# hdmi_transmitter.net
KiCad netlist of a schematic drawn in EAGLE
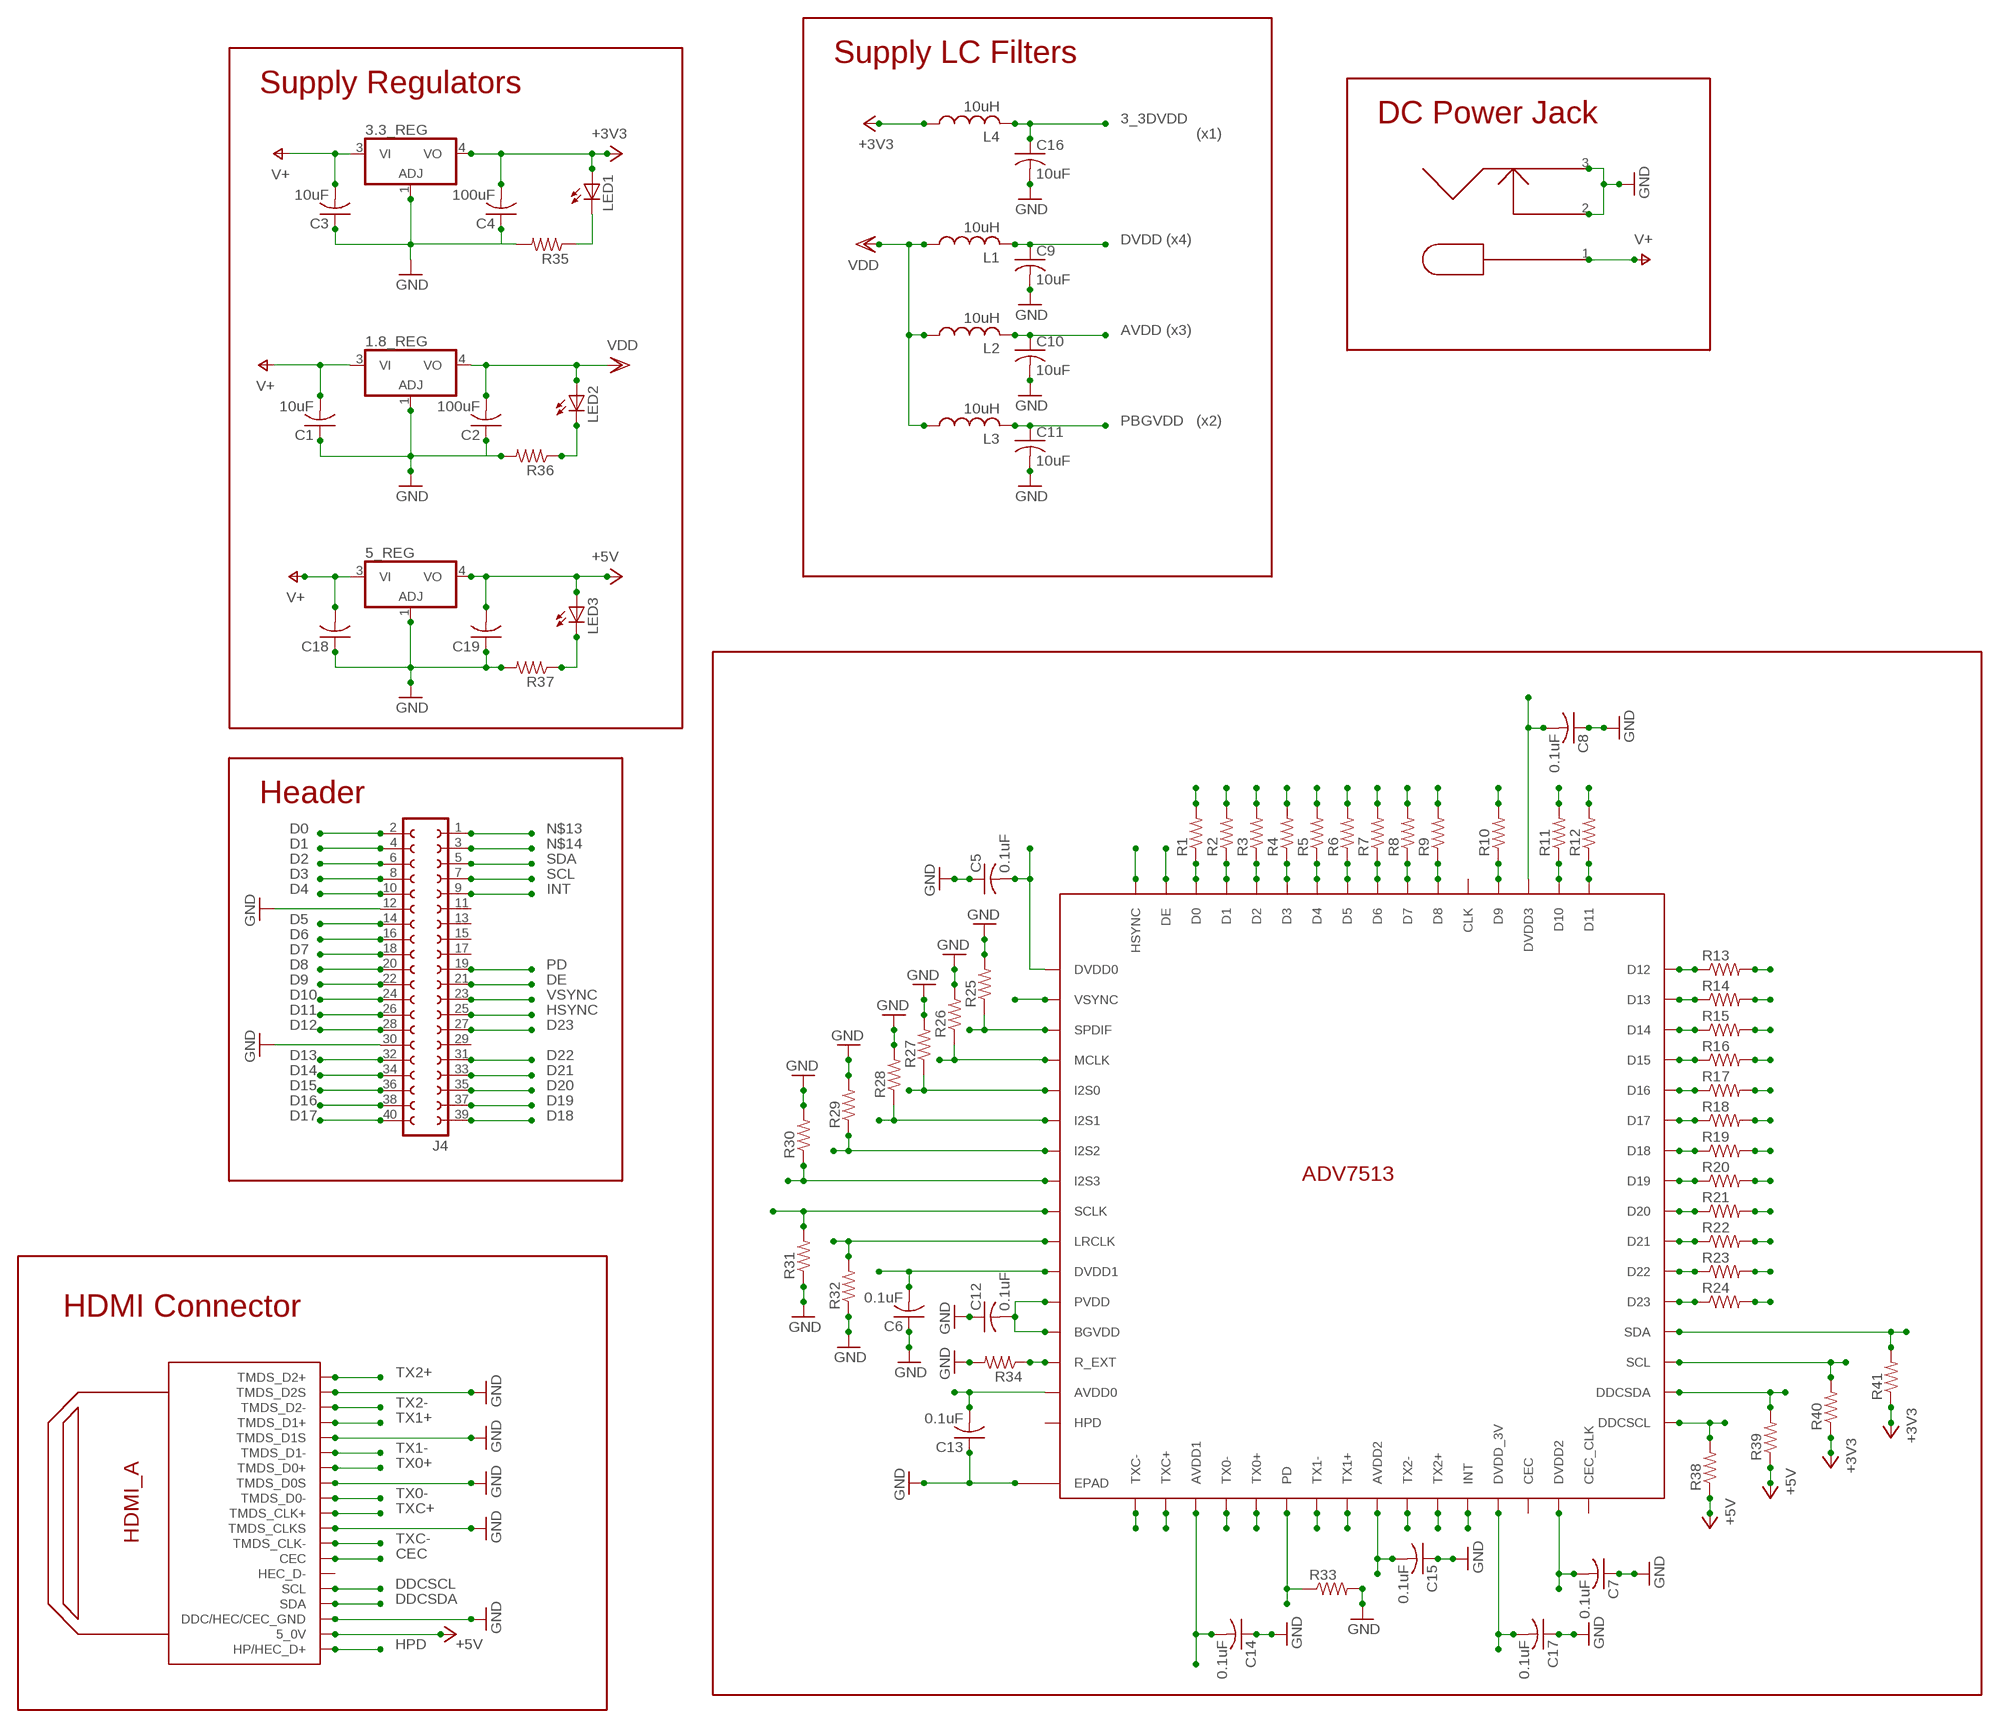
[diagram p0: schematic, sheet 1]

(export (version "E")
  (design (tool "Eeschema 10.0.6"))
  (components
    (comp (ref "1.8_REG")
      (value "317EMP")
      (footprint "eagle-import:SOT223")
      (libsource (lib "eagle-import") (part "317EMP"))
    )
    (comp (ref "3.3_REG")
      (value "317EMP")
      (footprint "eagle-import:SOT223")
      (libsource (lib "eagle-import") (part "317EMP"))
    )
    (comp (ref "5_REG")
      (value "317EMP")
      (footprint "eagle-import:SOT223")
      (libsource (lib "eagle-import") (part "317EMP"))
    )
    (comp (ref "C1")
      (value "10uF")
      (footprint "eagle-import:C0603")
      (libsource (lib "eagle-import") (part "C-USC0603"))
    )
    (comp (ref "C2")
      (value "100uF")
      (footprint "eagle-import:C0603")
      (libsource (lib "eagle-import") (part "C-USC0603"))
    )
    (comp (ref "C3")
      (value "10uF")
      (footprint "eagle-import:C0603")
      (libsource (lib "eagle-import") (part "C-USC0603"))
    )
    (comp (ref "C4")
      (value "100uF")
      (footprint "eagle-import:C0603")
      (libsource (lib "eagle-import") (part "C-USC0603"))
    )
    (comp (ref "C5")
      (value "0.1uF")
      (footprint "eagle-import:C0603")
      (libsource (lib "eagle-import") (part "C-USC0603"))
    )
    (comp (ref "C6")
      (value "0.1uF")
      (footprint "eagle-import:C0603")
      (libsource (lib "eagle-import") (part "C-USC0603"))
    )
    (comp (ref "C7")
      (value "0.1uF")
      (footprint "eagle-import:C0603")
      (libsource (lib "eagle-import") (part "C-USC0603"))
    )
    (comp (ref "C8")
      (value "0.1uF")
      (footprint "eagle-import:C0603")
      (libsource (lib "eagle-import") (part "C-USC0603"))
    )
    (comp (ref "C9")
      (value "10uF")
      (footprint "eagle-import:C0603")
      (libsource (lib "eagle-import") (part "C-USC0603"))
    )
    (comp (ref "C10")
      (value "10uF")
      (footprint "eagle-import:C0603")
      (libsource (lib "eagle-import") (part "C-USC0603"))
    )
    (comp (ref "C11")
      (value "10uF")
      (footprint "eagle-import:C0603")
      (libsource (lib "eagle-import") (part "C-USC0603"))
    )
    (comp (ref "C12")
      (value "0.1uF")
      (footprint "eagle-import:C0603")
      (libsource (lib "eagle-import") (part "C-USC0603"))
    )
    (comp (ref "C13")
      (value "0.1uF")
      (footprint "eagle-import:C0603")
      (libsource (lib "eagle-import") (part "C-USC0603"))
    )
    (comp (ref "C14")
      (value "0.1uF")
      (footprint "eagle-import:C0603")
      (libsource (lib "eagle-import") (part "C-USC0603"))
    )
    (comp (ref "C15")
      (value "0.1uF")
      (footprint "eagle-import:C0603")
      (libsource (lib "eagle-import") (part "C-USC0603"))
    )
    (comp (ref "C16")
      (value "10uF")
      (footprint "eagle-import:C0603")
      (libsource (lib "eagle-import") (part "C-USC0603"))
    )
    (comp (ref "C17")
      (value "0.1uF")
      (footprint "eagle-import:C0603")
      (libsource (lib "eagle-import") (part "C-USC0603"))
    )
    (comp (ref "C18")
      (value "C-USC0603")
      (footprint "eagle-import:C0603")
      (libsource (lib "eagle-import") (part "C-USC0603"))
    )
    (comp (ref "C19")
      (value "C-USC0603")
      (footprint "eagle-import:C0603")
      (libsource (lib "eagle-import") (part "C-USC0603"))
    )
    (comp (ref "J4")
      (value "FE20-2")
      (footprint "eagle-import:FE20-2")
      (libsource (lib "eagle-import") (part "FE20-2"))
    )
    (comp (ref "L1")
      (value "10uH")
      (footprint "eagle-import:L2012C")
      (libsource (lib "eagle-import") (part "L-USL2012C"))
    )
    (comp (ref "L2")
      (value "10uH")
      (footprint "eagle-import:L2012C")
      (libsource (lib "eagle-import") (part "L-USL2012C"))
    )
    (comp (ref "L3")
      (value "10uH")
      (footprint "eagle-import:L2012C")
      (libsource (lib "eagle-import") (part "L-USL2012C"))
    )
    (comp (ref "L4")
      (value "10uH")
      (footprint "eagle-import:L2012C")
      (libsource (lib "eagle-import") (part "L-USL2012C"))
    )
    (comp (ref "LED1")
      (value "LED5MM")
      (footprint "eagle-import:LED5MM")
      (libsource (lib "eagle-import") (part "LED5MM"))
    )
    (comp (ref "LED2")
      (value "LED5MM")
      (footprint "eagle-import:LED5MM")
      (libsource (lib "eagle-import") (part "LED5MM"))
    )
    (comp (ref "LED3")
      (value "LED5MM")
      (footprint "eagle-import:LED5MM")
      (libsource (lib "eagle-import") (part "LED5MM"))
    )
    (comp (ref "R1")
      (value "R-US_R0603")
      (footprint "eagle-import:R0603")
      (libsource (lib "eagle-import") (part "R-US_R0603"))
    )
    (comp (ref "R2")
      (value "R-US_R0603")
      (footprint "eagle-import:R0603")
      (libsource (lib "eagle-import") (part "R-US_R0603"))
    )
    (comp (ref "R3")
      (value "R-US_R0603")
      (footprint "eagle-import:R0603")
      (libsource (lib "eagle-import") (part "R-US_R0603"))
    )
    (comp (ref "R4")
      (value "R-US_R0603")
      (footprint "eagle-import:R0603")
      (libsource (lib "eagle-import") (part "R-US_R0603"))
    )
    (comp (ref "R5")
      (value "R-US_R0603")
      (footprint "eagle-import:R0603")
      (libsource (lib "eagle-import") (part "R-US_R0603"))
    )
    (comp (ref "R6")
      (value "R-US_R0603")
      (footprint "eagle-import:R0603")
      (libsource (lib "eagle-import") (part "R-US_R0603"))
    )
    (comp (ref "R7")
      (value "R-US_R0603")
      (footprint "eagle-import:R0603")
      (libsource (lib "eagle-import") (part "R-US_R0603"))
    )
    (comp (ref "R8")
      (value "R-US_R0603")
      (footprint "eagle-import:R0603")
      (libsource (lib "eagle-import") (part "R-US_R0603"))
    )
    (comp (ref "R9")
      (value "R-US_R0603")
      (footprint "eagle-import:R0603")
      (libsource (lib "eagle-import") (part "R-US_R0603"))
    )
    (comp (ref "R10")
      (value "R-US_R0603")
      (footprint "eagle-import:R0603")
      (libsource (lib "eagle-import") (part "R-US_R0603"))
    )
    (comp (ref "R11")
      (value "R-US_R0603")
      (footprint "eagle-import:R0603")
      (libsource (lib "eagle-import") (part "R-US_R0603"))
    )
    (comp (ref "R12")
      (value "R-US_R0603")
      (footprint "eagle-import:R0603")
      (libsource (lib "eagle-import") (part "R-US_R0603"))
    )
    (comp (ref "R13")
      (value "R-US_R0603")
      (footprint "eagle-import:R0603")
      (libsource (lib "eagle-import") (part "R-US_R0603"))
    )
    (comp (ref "R14")
      (value "R-US_R0603")
      (footprint "eagle-import:R0603")
      (libsource (lib "eagle-import") (part "R-US_R0603"))
    )
    (comp (ref "R15")
      (value "R-US_R0603")
      (footprint "eagle-import:R0603")
      (libsource (lib "eagle-import") (part "R-US_R0603"))
    )
    (comp (ref "R16")
      (value "R-US_R0603")
      (footprint "eagle-import:R0603")
      (libsource (lib "eagle-import") (part "R-US_R0603"))
    )
    (comp (ref "R17")
      (value "R-US_R0603")
      (footprint "eagle-import:R0603")
      (libsource (lib "eagle-import") (part "R-US_R0603"))
    )
    (comp (ref "R18")
      (value "R-US_R0603")
      (footprint "eagle-import:R0603")
      (libsource (lib "eagle-import") (part "R-US_R0603"))
    )
    (comp (ref "R19")
      (value "R-US_R0603")
      (footprint "eagle-import:R0603")
      (libsource (lib "eagle-import") (part "R-US_R0603"))
    )
    (comp (ref "R20")
      (value "R-US_R0603")
      (footprint "eagle-import:R0603")
      (libsource (lib "eagle-import") (part "R-US_R0603"))
    )
    (comp (ref "R21")
      (value "R-US_R0603")
      (footprint "eagle-import:R0603")
      (libsource (lib "eagle-import") (part "R-US_R0603"))
    )
    (comp (ref "R22")
      (value "R-US_R0603")
      (footprint "eagle-import:R0603")
      (libsource (lib "eagle-import") (part "R-US_R0603"))
    )
    (comp (ref "R23")
      (value "R-US_R0603")
      (footprint "eagle-import:R0603")
      (libsource (lib "eagle-import") (part "R-US_R0603"))
    )
    (comp (ref "R24")
      (value "R-US_R0603")
      (footprint "eagle-import:R0603")
      (libsource (lib "eagle-import") (part "R-US_R0603"))
    )
    (comp (ref "R25")
      (value "R-US_R0603")
      (footprint "eagle-import:R0603")
      (libsource (lib "eagle-import") (part "R-US_R0603"))
    )
    (comp (ref "R26")
      (value "R-US_R0603")
      (footprint "eagle-import:R0603")
      (libsource (lib "eagle-import") (part "R-US_R0603"))
    )
    (comp (ref "R27")
      (value "R-US_R0603")
      (footprint "eagle-import:R0603")
      (libsource (lib "eagle-import") (part "R-US_R0603"))
    )
    (comp (ref "R28")
      (value "R-US_R0603")
      (footprint "eagle-import:R0603")
      (libsource (lib "eagle-import") (part "R-US_R0603"))
    )
    (comp (ref "R29")
      (value "R-US_R0603")
      (footprint "eagle-import:R0603")
      (libsource (lib "eagle-import") (part "R-US_R0603"))
    )
    (comp (ref "R30")
      (value "R-US_R0603")
      (footprint "eagle-import:R0603")
      (libsource (lib "eagle-import") (part "R-US_R0603"))
    )
    (comp (ref "R31")
      (value "R-US_R0603")
      (footprint "eagle-import:R0603")
      (libsource (lib "eagle-import") (part "R-US_R0603"))
    )
    (comp (ref "R32")
      (value "R-US_R0603")
      (footprint "eagle-import:R0603")
      (libsource (lib "eagle-import") (part "R-US_R0603"))
    )
    (comp (ref "R33")
      (value "R-US_R0603")
      (footprint "eagle-import:R0603")
      (libsource (lib "eagle-import") (part "R-US_R0603"))
    )
    (comp (ref "R34")
      (value "R-US_R0603")
      (footprint "eagle-import:R0603")
      (libsource (lib "eagle-import") (part "R-US_R0603"))
    )
    (comp (ref "R35")
      (value "R-US_R0603")
      (footprint "eagle-import:R0603")
      (libsource (lib "eagle-import") (part "R-US_R0603"))
    )
    (comp (ref "R36")
      (value "R-US_R0603")
      (footprint "eagle-import:R0603")
      (libsource (lib "eagle-import") (part "R-US_R0603"))
    )
    (comp (ref "R37")
      (value "R-US_R0603")
      (footprint "eagle-import:R0603")
      (libsource (lib "eagle-import") (part "R-US_R0603"))
    )
    (comp (ref "R38")
      (value "R-US_R0603")
      (footprint "eagle-import:R0603")
      (libsource (lib "eagle-import") (part "R-US_R0603"))
    )
    (comp (ref "R39")
      (value "R-US_R0603")
      (footprint "eagle-import:R0603")
      (libsource (lib "eagle-import") (part "R-US_R0603"))
    )
    (comp (ref "R40")
      (value "R-US_R0603")
      (footprint "eagle-import:R0603")
      (libsource (lib "eagle-import") (part "R-US_R0603"))
    )
    (comp (ref "R41")
      (value "R-US_R0603")
      (footprint "eagle-import:R0603")
      (libsource (lib "eagle-import") (part "R-US_R0603"))
    )
    (comp (ref "U$1")
      (value "ADV7513")
      (footprint "eagle-import:LQFP-ST-64-2")
      (libsource (lib "eagle-import") (part "ADV7513"))
    )
    (comp (ref "U$2")
      (value "DC_BARREL_CONN")
      (footprint "eagle-import:DC_BARREL_CONN")
      (libsource (lib "eagle-import") (part "DC_BARREL_CONN"))
    )
    (comp (ref "U$3")
      (value "111RLF")
      (footprint "eagle-import:111RLF")
      (libsource (lib "eagle-import") (part "111RLF"))
    )
  )
  (nets
    (net (code "1") (name "+3V3") (class "Default")
      (node (ref "3.3_REG") (pin "4") (pinfunction "VO_4") (pintype "passive"))
      (node (ref "C4") (pin "2") (pinfunction "2_2") (pintype "passive"))
      (node (ref "L4") (pin "1") (pinfunction "1_1") (pintype "passive"))
      (node (ref "LED1") (pin "A") (pinfunction "A_A") (pintype "passive"))
      (node (ref "R40") (pin "1") (pinfunction "1_1") (pintype "passive"))
      (node (ref "R41") (pin "1") (pinfunction "1_1") (pintype "passive"))
    )
    (net (code "2") (name "+5V") (class "Default")
      (node (ref "5_REG") (pin "4") (pinfunction "VO_4") (pintype "passive"))
      (node (ref "C19") (pin "2") (pinfunction "2_2") (pintype "passive"))
      (node (ref "LED3") (pin "A") (pinfunction "A_A") (pintype "passive"))
      (node (ref "R38") (pin "1") (pinfunction "1_1") (pintype "passive"))
      (node (ref "R39") (pin "1") (pinfunction "1_1") (pintype "passive"))
      (node (ref "U$3") (pin "18") (pinfunction "5_0V_18") (pintype "bidirectional"))
    )
    (net (code "3") (name "/3_3DVDD") (class "Default")
      (node (ref "C16") (pin "1") (pinfunction "1_1") (pintype "passive"))
      (node (ref "C17") (pin "2") (pinfunction "2_2") (pintype "passive"))
      (node (ref "L4") (pin "2") (pinfunction "2_2") (pintype "passive"))
      (node (ref "U$1") (pin "29") (pinfunction "DVDD_3V_29") (pintype "bidirectional"))
    )
    (net (code "4") (name "/AVDD") (class "Default")
      (node (ref "C10") (pin "1") (pinfunction "1_1") (pintype "passive"))
      (node (ref "C13") (pin "2") (pinfunction "2_2") (pintype "passive"))
      (node (ref "C14") (pin "2") (pinfunction "2_2") (pintype "passive"))
      (node (ref "C15") (pin "2") (pinfunction "2_2") (pintype "passive"))
      (node (ref "L2") (pin "2") (pinfunction "2_2") (pintype "passive"))
      (node (ref "U$1") (pin "15") (pinfunction "AVDD0_15") (pintype "bidirectional"))
      (node (ref "U$1") (pin "19") (pinfunction "AVDD1_19") (pintype "bidirectional"))
      (node (ref "U$1") (pin "25") (pinfunction "AVDD2_25") (pintype "bidirectional"))
    )
    (net (code "5") (name "/CEC") (class "Default")
      (node (ref "U$3") (pin "13") (pinfunction "CEC_13") (pintype "bidirectional"))
    )
    (net (code "6") (name "/D0") (class "Default")
      (node (ref "J4") (pin "2") (pinfunction "2_2") (pintype "passive"))
      (node (ref "R1") (pin "2") (pinfunction "2_2") (pintype "passive"))
    )
    (net (code "7") (name "/D1") (class "Default")
      (node (ref "J4") (pin "4") (pinfunction "4_4") (pintype "passive"))
      (node (ref "R2") (pin "2") (pinfunction "2_2") (pintype "passive"))
    )
    (net (code "8") (name "/D2") (class "Default")
      (node (ref "J4") (pin "6") (pinfunction "6_6") (pintype "passive"))
      (node (ref "R3") (pin "2") (pinfunction "2_2") (pintype "passive"))
    )
    (net (code "9") (name "/D3") (class "Default")
      (node (ref "J4") (pin "8") (pinfunction "8_8") (pintype "passive"))
      (node (ref "R4") (pin "2") (pinfunction "2_2") (pintype "passive"))
    )
    (net (code "10") (name "/D4") (class "Default")
      (node (ref "J4") (pin "10") (pinfunction "10_10") (pintype "passive"))
      (node (ref "R5") (pin "2") (pinfunction "2_2") (pintype "passive"))
    )
    (net (code "11") (name "/D5") (class "Default")
      (node (ref "J4") (pin "14") (pinfunction "14_14") (pintype "passive"))
      (node (ref "R6") (pin "2") (pinfunction "2_2") (pintype "passive"))
    )
    (net (code "12") (name "/D6") (class "Default")
      (node (ref "J4") (pin "16") (pinfunction "16_16") (pintype "passive"))
      (node (ref "R7") (pin "2") (pinfunction "2_2") (pintype "passive"))
    )
    (net (code "13") (name "/D7") (class "Default")
      (node (ref "J4") (pin "18") (pinfunction "18_18") (pintype "passive"))
      (node (ref "R8") (pin "2") (pinfunction "2_2") (pintype "passive"))
    )
    (net (code "14") (name "/D8") (class "Default")
      (node (ref "J4") (pin "20") (pinfunction "20_20") (pintype "passive"))
      (node (ref "R9") (pin "2") (pinfunction "2_2") (pintype "passive"))
    )
    (net (code "15") (name "/D9") (class "Default")
      (node (ref "J4") (pin "22") (pinfunction "22_22") (pintype "passive"))
      (node (ref "R10") (pin "2") (pinfunction "2_2") (pintype "passive"))
    )
    (net (code "16") (name "/D10") (class "Default")
      (node (ref "J4") (pin "24") (pinfunction "24_24") (pintype "passive"))
      (node (ref "R11") (pin "2") (pinfunction "2_2") (pintype "passive"))
    )
    (net (code "17") (name "/D11") (class "Default")
      (node (ref "J4") (pin "26") (pinfunction "26_26") (pintype "passive"))
      (node (ref "R12") (pin "2") (pinfunction "2_2") (pintype "passive"))
    )
    (net (code "18") (name "/D12") (class "Default")
      (node (ref "J4") (pin "28") (pinfunction "28_28") (pintype "passive"))
      (node (ref "R13") (pin "2") (pinfunction "2_2") (pintype "passive"))
    )
    (net (code "19") (name "/D13") (class "Default")
      (node (ref "J4") (pin "32") (pinfunction "32_32") (pintype "passive"))
      (node (ref "R14") (pin "2") (pinfunction "2_2") (pintype "passive"))
    )
    (net (code "20") (name "/D14") (class "Default")
      (node (ref "J4") (pin "34") (pinfunction "34_34") (pintype "passive"))
      (node (ref "R15") (pin "2") (pinfunction "2_2") (pintype "passive"))
    )
    (net (code "21") (name "/D15") (class "Default")
      (node (ref "J4") (pin "36") (pinfunction "36_36") (pintype "passive"))
      (node (ref "R16") (pin "2") (pinfunction "2_2") (pintype "passive"))
    )
    (net (code "22") (name "/D16") (class "Default")
      (node (ref "J4") (pin "38") (pinfunction "38_38") (pintype "passive"))
      (node (ref "R17") (pin "2") (pinfunction "2_2") (pintype "passive"))
    )
    (net (code "23") (name "/D17") (class "Default")
      (node (ref "J4") (pin "40") (pinfunction "40_40") (pintype "passive"))
      (node (ref "R18") (pin "2") (pinfunction "2_2") (pintype "passive"))
    )
    (net (code "24") (name "/D18") (class "Default")
      (node (ref "J4") (pin "39") (pinfunction "39_39") (pintype "passive"))
      (node (ref "R19") (pin "2") (pinfunction "2_2") (pintype "passive"))
    )
    (net (code "25") (name "/D19") (class "Default")
      (node (ref "J4") (pin "37") (pinfunction "37_37") (pintype "passive"))
      (node (ref "R20") (pin "2") (pinfunction "2_2") (pintype "passive"))
    )
    (net (code "26") (name "/D20") (class "Default")
      (node (ref "J4") (pin "35") (pinfunction "35_35") (pintype "passive"))
      (node (ref "R21") (pin "2") (pinfunction "2_2") (pintype "passive"))
    )
    (net (code "27") (name "/D21") (class "Default")
      (node (ref "J4") (pin "33") (pinfunction "33_33") (pintype "passive"))
      (node (ref "R22") (pin "2") (pinfunction "2_2") (pintype "passive"))
    )
    (net (code "28") (name "/D22") (class "Default")
      (node (ref "J4") (pin "31") (pinfunction "31_31") (pintype "passive"))
      (node (ref "R23") (pin "2") (pinfunction "2_2") (pintype "passive"))
    )
    (net (code "29") (name "/D23") (class "Default")
      (node (ref "J4") (pin "27") (pinfunction "27_27") (pintype "passive"))
      (node (ref "R24") (pin "2") (pinfunction "2_2") (pintype "passive"))
    )
    (net (code "30") (name "/DDCSCL") (class "Default")
      (node (ref "R38") (pin "2") (pinfunction "2_2") (pintype "passive"))
      (node (ref "U$1") (pin "33") (pinfunction "DDCSCL_33") (pintype "bidirectional"))
      (node (ref "U$3") (pin "15") (pinfunction "SCL_15") (pintype "bidirectional"))
    )
    (net (code "31") (name "/DDCSDA") (class "Default")
      (node (ref "R39") (pin "2") (pinfunction "2_2") (pintype "passive"))
      (node (ref "U$1") (pin "34") (pinfunction "DDCSDA_34") (pintype "bidirectional"))
      (node (ref "U$3") (pin "16") (pinfunction "SDA_16") (pintype "bidirectional"))
    )
    (net (code "32") (name "/DE") (class "Default")
      (node (ref "J4") (pin "21") (pinfunction "21_21") (pintype "passive"))
      (node (ref "U$1") (pin "63") (pinfunction "DE_63") (pintype "bidirectional"))
    )
    (net (code "33") (name "/DVDD") (class "Default")
      (node (ref "C5") (pin "2") (pinfunction "2_2") (pintype "passive"))
      (node (ref "C6") (pin "2") (pinfunction "2_2") (pintype "passive"))
      (node (ref "C7") (pin "2") (pinfunction "2_2") (pintype "passive"))
      (node (ref "C8") (pin "2") (pinfunction "2_2") (pintype "passive"))
      (node (ref "C9") (pin "1") (pinfunction "1_1") (pintype "passive"))
      (node (ref "L1") (pin "2") (pinfunction "2_2") (pintype "passive"))
      (node (ref "U$1") (pin "1") (pinfunction "DVDD0_1") (pintype "bidirectional"))
      (node (ref "U$1") (pin "11") (pinfunction "DVDD1_11") (pintype "bidirectional"))
      (node (ref "U$1") (pin "31") (pinfunction "DVDD2_31") (pintype "bidirectional"))
      (node (ref "U$1") (pin "51") (pinfunction "DVDD3_51") (pintype "bidirectional"))
    )
    (net (code "34") (name "/HPD") (class "Default")
      (node (ref "U$3") (pin "19") (pinfunction "HP/HEC_D+_19") (pintype "bidirectional"))
    )
    (net (code "35") (name "/HSYNC") (class "Default")
      (node (ref "J4") (pin "25") (pinfunction "25_25") (pintype "passive"))
      (node (ref "U$1") (pin "64") (pinfunction "HSYNC_64") (pintype "bidirectional"))
    )
    (net (code "36") (name "/INT") (class "Default")
      (node (ref "J4") (pin "9") (pinfunction "9_9") (pintype "passive"))
      (node (ref "U$1") (pin "28") (pinfunction "INT_28") (pintype "bidirectional"))
    )
    (net (code "37") (name "/N$13") (class "Default")
      (node (ref "J4") (pin "1") (pinfunction "1_1") (pintype "passive"))
    )
    (net (code "38") (name "/N$14") (class "Default")
      (node (ref "J4") (pin "3") (pinfunction "3_3") (pintype "passive"))
    )
    (net (code "39") (name "/PBGVDD") (class "Default")
      (node (ref "C11") (pin "1") (pinfunction "1_1") (pintype "passive"))
      (node (ref "C12") (pin "2") (pinfunction "2_2") (pintype "passive"))
      (node (ref "L3") (pin "2") (pinfunction "2_2") (pintype "passive"))
      (node (ref "U$1") (pin "12") (pinfunction "PVDD_12") (pintype "bidirectional"))
      (node (ref "U$1") (pin "13") (pinfunction "BGVDD_13") (pintype "bidirectional"))
    )
    (net (code "40") (name "/PD") (class "Default")
      (node (ref "J4") (pin "19") (pinfunction "19_19") (pintype "passive"))
      (node (ref "R33") (pin "1") (pinfunction "1_1") (pintype "passive"))
      (node (ref "U$1") (pin "22") (pinfunction "PD_22") (pintype "bidirectional"))
    )
    (net (code "41") (name "/SCL") (class "Default")
      (node (ref "J4") (pin "7") (pinfunction "7_7") (pintype "passive"))
      (node (ref "R40") (pin "2") (pinfunction "2_2") (pintype "passive"))
      (node (ref "U$1") (pin "35") (pinfunction "SCL_35") (pintype "bidirectional"))
    )
    (net (code "42") (name "/SDA") (class "Default")
      (node (ref "J4") (pin "5") (pinfunction "5_5") (pintype "passive"))
      (node (ref "R41") (pin "2") (pinfunction "2_2") (pintype "passive"))
      (node (ref "U$1") (pin "36") (pinfunction "SDA_36") (pintype "bidirectional"))
    )
    (net (code "43") (name "/TX0+") (class "Default")
      (node (ref "U$1") (pin "21") (pinfunction "TX0+_21") (pintype "bidirectional"))
      (node (ref "U$3") (pin "7") (pinfunction "TMDS_D0+_7") (pintype "bidirectional"))
    )
    (net (code "44") (name "/TX0-") (class "Default")
      (node (ref "U$1") (pin "20") (pinfunction "TX0-_20") (pintype "bidirectional"))
      (node (ref "U$3") (pin "9") (pinfunction "TMDS_D0-_9") (pintype "bidirectional"))
    )
    (net (code "45") (name "/TX1+") (class "Default")
      (node (ref "U$1") (pin "24") (pinfunction "TX1+_24") (pintype "bidirectional"))
      (node (ref "U$3") (pin "4") (pinfunction "TMDS_D1+_4") (pintype "bidirectional"))
    )
    (net (code "46") (name "/TX1-") (class "Default")
      (node (ref "U$1") (pin "23") (pinfunction "TX1-_23") (pintype "bidirectional"))
      (node (ref "U$3") (pin "6") (pinfunction "TMDS_D1-_6") (pintype "bidirectional"))
    )
    (net (code "47") (name "/TX2+") (class "Default")
      (node (ref "U$1") (pin "27") (pinfunction "TX2+_27") (pintype "bidirectional"))
      (node (ref "U$3") (pin "1") (pinfunction "TMDS_D2+_1") (pintype "bidirectional"))
    )
    (net (code "48") (name "/TX2-") (class "Default")
      (node (ref "U$1") (pin "26") (pinfunction "TX2-_26") (pintype "bidirectional"))
      (node (ref "U$3") (pin "3") (pinfunction "TMDS_D2-_3") (pintype "bidirectional"))
    )
    (net (code "49") (name "/TXC+") (class "Default")
      (node (ref "U$1") (pin "18") (pinfunction "TXC+_18") (pintype "bidirectional"))
      (node (ref "U$3") (pin "10") (pinfunction "TMDS_CLK+_10") (pintype "bidirectional"))
    )
    (net (code "50") (name "/TXC-") (class "Default")
      (node (ref "U$1") (pin "17") (pinfunction "TXC-_17") (pintype "bidirectional"))
      (node (ref "U$3") (pin "12") (pinfunction "TMDS_CLK-_12") (pintype "bidirectional"))
    )
    (net (code "51") (name "/VSYNC") (class "Default")
      (node (ref "J4") (pin "23") (pinfunction "23_23") (pintype "passive"))
      (node (ref "U$1") (pin "2") (pinfunction "VSYNC_2") (pintype "bidirectional"))
    )
    (net (code "52") (name "GND") (class "Default")
      (node (ref "1.8_REG") (pin "1") (pinfunction "ADJ_1") (pintype "input"))
      (node (ref "3.3_REG") (pin "1") (pinfunction "ADJ_1") (pintype "input"))
      (node (ref "5_REG") (pin "1") (pinfunction "ADJ_1") (pintype "input"))
      (node (ref "C1") (pin "1") (pinfunction "1_1") (pintype "passive"))
      (node (ref "C10") (pin "2") (pinfunction "2_2") (pintype "passive"))
      (node (ref "C11") (pin "2") (pinfunction "2_2") (pintype "passive"))
      (node (ref "C12") (pin "1") (pinfunction "1_1") (pintype "passive"))
      (node (ref "C13") (pin "1") (pinfunction "1_1") (pintype "passive"))
      (node (ref "C14") (pin "1") (pinfunction "1_1") (pintype "passive"))
      (node (ref "C15") (pin "1") (pinfunction "1_1") (pintype "passive"))
      (node (ref "C16") (pin "2") (pinfunction "2_2") (pintype "passive"))
      (node (ref "C17") (pin "1") (pinfunction "1_1") (pintype "passive"))
      (node (ref "C18") (pin "1") (pinfunction "1_1") (pintype "passive"))
      (node (ref "C19") (pin "1") (pinfunction "1_1") (pintype "passive"))
      (node (ref "C2") (pin "1") (pinfunction "1_1") (pintype "passive"))
      (node (ref "C3") (pin "1") (pinfunction "1_1") (pintype "passive"))
      (node (ref "C4") (pin "1") (pinfunction "1_1") (pintype "passive"))
      (node (ref "C5") (pin "1") (pinfunction "1_1") (pintype "passive"))
      (node (ref "C6") (pin "1") (pinfunction "1_1") (pintype "passive"))
      (node (ref "C7") (pin "1") (pinfunction "1_1") (pintype "passive"))
      (node (ref "C8") (pin "1") (pinfunction "1_1") (pintype "passive"))
      (node (ref "C9") (pin "2") (pinfunction "2_2") (pintype "passive"))
      (node (ref "J4") (pin "12") (pinfunction "12_12") (pintype "passive"))
      (node (ref "J4") (pin "30") (pinfunction "30_30") (pintype "passive"))
      (node (ref "R25") (pin "2") (pinfunction "2_2") (pintype "passive"))
      (node (ref "R26") (pin "2") (pinfunction "2_2") (pintype "passive"))
      (node (ref "R27") (pin "2") (pinfunction "2_2") (pintype "passive"))
      (node (ref "R28") (pin "2") (pinfunction "2_2") (pintype "passive"))
      (node (ref "R29") (pin "2") (pinfunction "2_2") (pintype "passive"))
      (node (ref "R30") (pin "2") (pinfunction "2_2") (pintype "passive"))
      (node (ref "R31") (pin "1") (pinfunction "1_1") (pintype "passive"))
      (node (ref "R32") (pin "1") (pinfunction "1_1") (pintype "passive"))
      (node (ref "R33") (pin "2") (pinfunction "2_2") (pintype "passive"))
      (node (ref "R34") (pin "2") (pinfunction "2_2") (pintype "passive"))
      (node (ref "R35") (pin "2") (pinfunction "2_2") (pintype "passive"))
      (node (ref "R36") (pin "2") (pinfunction "2_2") (pintype "passive"))
      (node (ref "R37") (pin "2") (pinfunction "2_2") (pintype "passive"))
      (node (ref "U$1") (pin "0") (pinfunction "EPAD_0") (pintype "bidirectional"))
      (node (ref "U$2") (pin "2") (pinfunction "2_2") (pintype "bidirectional"))
      (node (ref "U$2") (pin "3") (pinfunction "3_3") (pintype "bidirectional"))
      (node (ref "U$3") (pin "11") (pinfunction "TMDS_CLKS_11") (pintype "bidirectional"))
      (node (ref "U$3") (pin "17") (pinfunction "DDC/HEC/CEC_GND_17") (pintype "bidirectional"))
      (node (ref "U$3") (pin "2") (pinfunction "TMDS_D2S_2") (pintype "bidirectional"))
      (node (ref "U$3") (pin "5") (pinfunction "TMDS_D1S_5") (pintype "bidirectional"))
      (node (ref "U$3") (pin "8") (pinfunction "TMDS_D0S_8") (pintype "bidirectional"))
    )
    (net (code "53") (name "Net-(LED1-C)") (class "Default")
      (node (ref "LED1") (pin "K") (pinfunction "C_K") (pintype "passive"))
      (node (ref "R35") (pin "1") (pinfunction "1_1") (pintype "passive"))
    )
    (net (code "54") (name "Net-(LED2-C)") (class "Default")
      (node (ref "LED2") (pin "K") (pinfunction "C_K") (pintype "passive"))
      (node (ref "R36") (pin "1") (pinfunction "1_1") (pintype "passive"))
    )
    (net (code "55") (name "Net-(LED3-C)") (class "Default")
      (node (ref "LED3") (pin "K") (pinfunction "C_K") (pintype "passive"))
      (node (ref "R37") (pin "1") (pinfunction "1_1") (pintype "passive"))
    )
    (net (code "56") (name "Net-(U$1-D0)") (class "Default")
      (node (ref "R1") (pin "1") (pinfunction "1_1") (pintype "passive"))
      (node (ref "U$1") (pin "62") (pinfunction "D0_62") (pintype "bidirectional"))
    )
    (net (code "57") (name "Net-(U$1-D1)") (class "Default")
      (node (ref "R2") (pin "1") (pinfunction "1_1") (pintype "passive"))
      (node (ref "U$1") (pin "61") (pinfunction "D1_61") (pintype "bidirectional"))
    )
    (net (code "58") (name "Net-(U$1-D2)") (class "Default")
      (node (ref "R3") (pin "1") (pinfunction "1_1") (pintype "passive"))
      (node (ref "U$1") (pin "60") (pinfunction "D2_60") (pintype "bidirectional"))
    )
    (net (code "59") (name "Net-(U$1-D3)") (class "Default")
      (node (ref "R4") (pin "1") (pinfunction "1_1") (pintype "passive"))
      (node (ref "U$1") (pin "59") (pinfunction "D3_59") (pintype "bidirectional"))
    )
    (net (code "60") (name "Net-(U$1-D4)") (class "Default")
      (node (ref "R5") (pin "1") (pinfunction "1_1") (pintype "passive"))
      (node (ref "U$1") (pin "58") (pinfunction "D4_58") (pintype "bidirectional"))
    )
    (net (code "61") (name "Net-(U$1-D5)") (class "Default")
      (node (ref "R6") (pin "1") (pinfunction "1_1") (pintype "passive"))
      (node (ref "U$1") (pin "57") (pinfunction "D5_57") (pintype "bidirectional"))
    )
    (net (code "62") (name "Net-(U$1-D6)") (class "Default")
      (node (ref "R7") (pin "1") (pinfunction "1_1") (pintype "passive"))
      (node (ref "U$1") (pin "56") (pinfunction "D6_56") (pintype "bidirectional"))
    )
    (net (code "63") (name "Net-(U$1-D7)") (class "Default")
      (node (ref "R8") (pin "1") (pinfunction "1_1") (pintype "passive"))
      (node (ref "U$1") (pin "55") (pinfunction "D7_55") (pintype "bidirectional"))
    )
    (net (code "64") (name "Net-(U$1-D8)") (class "Default")
      (node (ref "R9") (pin "1") (pinfunction "1_1") (pintype "passive"))
      (node (ref "U$1") (pin "54") (pinfunction "D8_54") (pintype "bidirectional"))
    )
    (net (code "65") (name "Net-(U$1-D9)") (class "Default")
      (node (ref "R10") (pin "1") (pinfunction "1_1") (pintype "passive"))
      (node (ref "U$1") (pin "52") (pinfunction "D9_52") (pintype "bidirectional"))
    )
    (net (code "66") (name "Net-(U$1-D10)") (class "Default")
      (node (ref "R11") (pin "1") (pinfunction "1_1") (pintype "passive"))
      (node (ref "U$1") (pin "50") (pinfunction "D10_50") (pintype "bidirectional"))
    )
    (net (code "67") (name "Net-(U$1-D11)") (class "Default")
      (node (ref "R12") (pin "1") (pinfunction "1_1") (pintype "passive"))
      (node (ref "U$1") (pin "49") (pinfunction "D11_49") (pintype "bidirectional"))
    )
    (net (code "68") (name "Net-(U$1-D12)") (class "Default")
      (node (ref "R13") (pin "1") (pinfunction "1_1") (pintype "passive"))
      (node (ref "U$1") (pin "48") (pinfunction "D12_48") (pintype "bidirectional"))
    )
    (net (code "69") (name "Net-(U$1-D13)") (class "Default")
      (node (ref "R14") (pin "1") (pinfunction "1_1") (pintype "passive"))
      (node (ref "U$1") (pin "47") (pinfunction "D13_47") (pintype "bidirectional"))
    )
    (net (code "70") (name "Net-(U$1-D14)") (class "Default")
      (node (ref "R15") (pin "1") (pinfunction "1_1") (pintype "passive"))
      (node (ref "U$1") (pin "46") (pinfunction "D14_46") (pintype "bidirectional"))
    )
    (net (code "71") (name "Net-(U$1-D15)") (class "Default")
      (node (ref "R16") (pin "1") (pinfunction "1_1") (pintype "passive"))
      (node (ref "U$1") (pin "45") (pinfunction "D15_45") (pintype "bidirectional"))
    )
    (net (code "72") (name "Net-(U$1-D16)") (class "Default")
      (node (ref "R17") (pin "1") (pinfunction "1_1") (pintype "passive"))
      (node (ref "U$1") (pin "44") (pinfunction "D16_44") (pintype "bidirectional"))
    )
    (net (code "73") (name "Net-(U$1-D17)") (class "Default")
      (node (ref "R18") (pin "1") (pinfunction "1_1") (pintype "passive"))
      (node (ref "U$1") (pin "43") (pinfunction "D17_43") (pintype "bidirectional"))
    )
    (net (code "74") (name "Net-(U$1-D18)") (class "Default")
      (node (ref "R19") (pin "1") (pinfunction "1_1") (pintype "passive"))
      (node (ref "U$1") (pin "42") (pinfunction "D18_42") (pintype "bidirectional"))
    )
    (net (code "75") (name "Net-(U$1-D19)") (class "Default")
      (node (ref "R20") (pin "1") (pinfunction "1_1") (pintype "passive"))
      (node (ref "U$1") (pin "41") (pinfunction "D19_41") (pintype "bidirectional"))
    )
    (net (code "76") (name "Net-(U$1-D20)") (class "Default")
      (node (ref "R21") (pin "1") (pinfunction "1_1") (pintype "passive"))
      (node (ref "U$1") (pin "40") (pinfunction "D20_40") (pintype "bidirectional"))
    )
    (net (code "77") (name "Net-(U$1-D21)") (class "Default")
      (node (ref "R22") (pin "1") (pinfunction "1_1") (pintype "passive"))
      (node (ref "U$1") (pin "39") (pinfunction "D21_39") (pintype "bidirectional"))
    )
    (net (code "78") (name "Net-(U$1-D22)") (class "Default")
      (node (ref "R23") (pin "1") (pinfunction "1_1") (pintype "passive"))
      (node (ref "U$1") (pin "38") (pinfunction "D22_38") (pintype "bidirectional"))
    )
    (net (code "79") (name "Net-(U$1-D23)") (class "Default")
      (node (ref "R24") (pin "1") (pinfunction "1_1") (pintype "passive"))
      (node (ref "U$1") (pin "37") (pinfunction "D23_37") (pintype "bidirectional"))
    )
    (net (code "80") (name "Net-(U$1-I2S0)") (class "Default")
      (node (ref "R27") (pin "1") (pinfunction "1_1") (pintype "passive"))
      (node (ref "U$1") (pin "5") (pinfunction "I2S0_5") (pintype "bidirectional"))
    )
    (net (code "81") (name "Net-(U$1-I2S1)") (class "Default")
      (node (ref "R28") (pin "1") (pinfunction "1_1") (pintype "passive"))
      (node (ref "U$1") (pin "6") (pinfunction "I2S1_6") (pintype "bidirectional"))
    )
    (net (code "82") (name "Net-(U$1-I2S2)") (class "Default")
      (node (ref "R29") (pin "1") (pinfunction "1_1") (pintype "passive"))
      (node (ref "U$1") (pin "7") (pinfunction "I2S2_7") (pintype "bidirectional"))
    )
    (net (code "83") (name "Net-(U$1-I2S3)") (class "Default")
      (node (ref "R30") (pin "1") (pinfunction "1_1") (pintype "passive"))
      (node (ref "U$1") (pin "8") (pinfunction "I2S3_8") (pintype "bidirectional"))
    )
    (net (code "84") (name "Net-(U$1-LRCLK)") (class "Default")
      (node (ref "R32") (pin "2") (pinfunction "2_2") (pintype "passive"))
      (node (ref "U$1") (pin "10") (pinfunction "LRCLK_10") (pintype "bidirectional"))
    )
    (net (code "85") (name "Net-(U$1-MCLK)") (class "Default")
      (node (ref "R26") (pin "1") (pinfunction "1_1") (pintype "passive"))
      (node (ref "U$1") (pin "4") (pinfunction "MCLK_4") (pintype "bidirectional"))
    )
    (net (code "86") (name "Net-(U$1-R_EXT)") (class "Default")
      (node (ref "R34") (pin "1") (pinfunction "1_1") (pintype "passive"))
      (node (ref "U$1") (pin "14") (pinfunction "R_EXT_14") (pintype "bidirectional"))
    )
    (net (code "87") (name "Net-(U$1-SCLK)") (class "Default")
      (node (ref "R31") (pin "2") (pinfunction "2_2") (pintype "passive"))
      (node (ref "U$1") (pin "9") (pinfunction "SCLK_9") (pintype "bidirectional"))
    )
    (net (code "88") (name "Net-(U$1-SPDIF)") (class "Default")
      (node (ref "R25") (pin "1") (pinfunction "1_1") (pintype "passive"))
      (node (ref "U$1") (pin "3") (pinfunction "SPDIF_3") (pintype "bidirectional"))
    )
    (net (code "89") (name "V+") (class "Default")
      (node (ref "1.8_REG") (pin "3") (pinfunction "VI_3") (pintype "input"))
      (node (ref "3.3_REG") (pin "3") (pinfunction "VI_3") (pintype "input"))
      (node (ref "5_REG") (pin "3") (pinfunction "VI_3") (pintype "input"))
      (node (ref "C1") (pin "2") (pinfunction "2_2") (pintype "passive"))
      (node (ref "C18") (pin "2") (pinfunction "2_2") (pintype "passive"))
      (node (ref "C3") (pin "2") (pinfunction "2_2") (pintype "passive"))
      (node (ref "U$2") (pin "1") (pinfunction "1_1") (pintype "bidirectional"))
    )
    (net (code "90") (name "VDD") (class "Default")
      (node (ref "1.8_REG") (pin "4") (pinfunction "VO_4") (pintype "passive"))
      (node (ref "C2") (pin "2") (pinfunction "2_2") (pintype "passive"))
      (node (ref "L1") (pin "1") (pinfunction "1_1") (pintype "passive"))
      (node (ref "L2") (pin "1") (pinfunction "1_1") (pintype "passive"))
      (node (ref "L3") (pin "1") (pinfunction "1_1") (pintype "passive"))
      (node (ref "LED2") (pin "A") (pinfunction "A_A") (pintype "passive"))
    )
    (net (code "91") (name "unconnected-(J4-Pad11)") (class "Default")
      (node (ref "J4") (pin "11") (pinfunction "11_11") (pintype "passive"))
    )
    (net (code "92") (name "unconnected-(J4-Pad13)") (class "Default")
      (node (ref "J4") (pin "13") (pinfunction "13_13") (pintype "passive"))
    )
    (net (code "93") (name "unconnected-(J4-Pad15)") (class "Default")
      (node (ref "J4") (pin "15") (pinfunction "15_15") (pintype "passive"))
    )
    (net (code "94") (name "unconnected-(J4-Pad17)") (class "Default")
      (node (ref "J4") (pin "17") (pinfunction "17_17") (pintype "passive"))
    )
    (net (code "95") (name "unconnected-(J4-Pad29)") (class "Default")
      (node (ref "J4") (pin "29") (pinfunction "29_29") (pintype "passive"))
    )
    (net (code "96") (name "unconnected-(U$1-CEC-Pad30)") (class "Default")
      (node (ref "U$1") (pin "30") (pinfunction "CEC_30") (pintype "bidirectional"))
    )
    (net (code "97") (name "unconnected-(U$1-CEC_CLK-Pad32)") (class "Default")
      (node (ref "U$1") (pin "32") (pinfunction "CEC_CLK_32") (pintype "bidirectional"))
    )
    (net (code "98") (name "unconnected-(U$1-CLK-Pad53)") (class "Default")
      (node (ref "U$1") (pin "53") (pinfunction "CLK_53") (pintype "bidirectional"))
    )
    (net (code "99") (name "unconnected-(U$1-HPD-Pad16)") (class "Default")
      (node (ref "U$1") (pin "16") (pinfunction "HPD_16") (pintype "bidirectional"))
    )
    (net (code "100") (name "unconnected-(U$3-HEC_D--Pad14)") (class "Default")
      (node (ref "U$3") (pin "14") (pinfunction "HEC_D-_14") (pintype "bidirectional"))
    )
  )
)
